# SCD4X-Grove.net
KiCad netlist of a schematic drawn in EAGLE
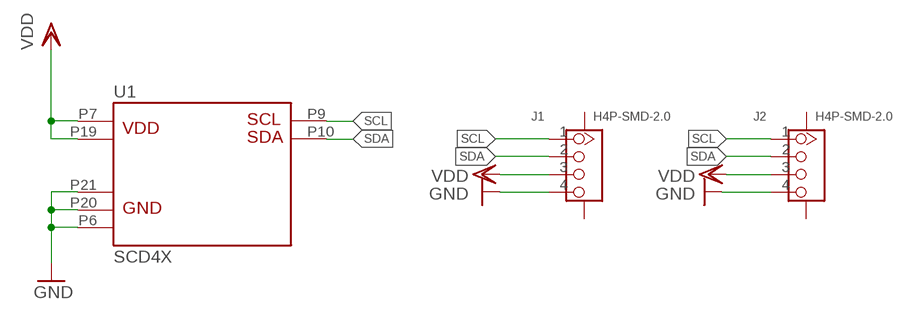
[diagram p0: schematic, sheet 1]

(export (version "E")
  (design (tool "Eeschema 10.0.6"))
  (components
    (comp (ref "J1")
      (value "H4P-SMD-2.0")
      (footprint "eagle-import:HW4-SMD-2.0")
      (libsource (lib "eagle-import") (part "GROVE-CONNECTOR-SMD(4+2P-2.0)"))
    )
    (comp (ref "J2")
      (value "H4P-SMD-2.0")
      (footprint "eagle-import:HW4-SMD-2.0")
      (libsource (lib "eagle-import") (part "GROVE-CONNECTOR-SMD(4+2P-2.0)"))
    )
    (comp (ref "U1")
      (value "SCD4X")
      (footprint "eagle-import:SCD4X")
      (libsource (lib "eagle-import") (part "SCD4X"))
    )
  )
  (nets
    (net (code "1") (name "GND") (class "Default")
      (node (ref "J1") (pin "4") (pinfunction "4_4") (pintype "bidirectional"))
      (node (ref "J2") (pin "4") (pinfunction "4_4") (pintype "bidirectional"))
      (node (ref "U1") (pin "P20") (pinfunction "P$20_P20") (pintype "power_in"))
      (node (ref "U1") (pin "P21") (pinfunction "P$21_P21") (pintype "power_in"))
      (node (ref "U1") (pin "P6") (pinfunction "P$6_P6") (pintype "power_in"))
    )
    (net (code "2") (name "SCL") (class "Default")
      (node (ref "J1") (pin "1") (pinfunction "1_1") (pintype "bidirectional"))
      (node (ref "J2") (pin "1") (pinfunction "1_1") (pintype "bidirectional"))
      (node (ref "U1") (pin "P9") (pinfunction "P$9_P9") (pintype "bidirectional"))
    )
    (net (code "3") (name "SDA") (class "Default")
      (node (ref "J1") (pin "2") (pinfunction "2_2") (pintype "bidirectional"))
      (node (ref "J2") (pin "2") (pinfunction "2_2") (pintype "bidirectional"))
      (node (ref "U1") (pin "P10") (pinfunction "P$10_P10") (pintype "bidirectional"))
    )
    (net (code "4") (name "VDD") (class "Default")
      (node (ref "J1") (pin "3") (pinfunction "3_3") (pintype "bidirectional"))
      (node (ref "J2") (pin "3") (pinfunction "3_3") (pintype "bidirectional"))
      (node (ref "U1") (pin "P19") (pinfunction "P$19_P19") (pintype "power_in"))
      (node (ref "U1") (pin "P7") (pinfunction "P$7_P7") (pintype "power_in"))
    )
    (net (code "5") (name "unconnected-(J1-PadSS1)") (class "Default")
      (node (ref "J1") (pin "SS1") (pinfunction "SS1_SS1") (pintype "bidirectional"))
    )
    (net (code "6") (name "unconnected-(J1-PadSS2)") (class "Default")
      (node (ref "J1") (pin "SS2") (pinfunction "SS2_SS2") (pintype "bidirectional"))
    )
    (net (code "7") (name "unconnected-(J2-PadSS1)") (class "Default")
      (node (ref "J2") (pin "SS1") (pinfunction "SS1_SS1") (pintype "bidirectional"))
    )
    (net (code "8") (name "unconnected-(J2-PadSS2)") (class "Default")
      (node (ref "J2") (pin "SS2") (pinfunction "SS2_SS2") (pintype "bidirectional"))
    )
    (net (code "9") (name "unconnected-(U1-P$1-PadP1)") (class "Default")
      (node (ref "U1") (pin "P1") (pinfunction "P$1_P1") (pintype "no_connect"))
    )
    (net (code "10") (name "unconnected-(U1-P$2-PadP2)") (class "Default")
      (node (ref "U1") (pin "P2") (pinfunction "P$2_P2") (pintype "no_connect"))
    )
    (net (code "11") (name "unconnected-(U1-P$3-PadP3)") (class "Default")
      (node (ref "U1") (pin "P3") (pinfunction "P$3_P3") (pintype "no_connect"))
    )
    (net (code "12") (name "unconnected-(U1-P$4-PadP4)") (class "Default")
      (node (ref "U1") (pin "P4") (pinfunction "P$4_P4") (pintype "no_connect"))
    )
    (net (code "13") (name "unconnected-(U1-P$5-PadP5)") (class "Default")
      (node (ref "U1") (pin "P5") (pinfunction "P$5_P5") (pintype "no_connect"))
    )
    (net (code "14") (name "unconnected-(U1-P$8-PadP8)") (class "Default")
      (node (ref "U1") (pin "P8") (pinfunction "P$8_P8") (pintype "no_connect"))
    )
    (net (code "15") (name "unconnected-(U1-P$11-PadP11)") (class "Default")
      (node (ref "U1") (pin "P11") (pinfunction "P$11_P11") (pintype "no_connect"))
    )
    (net (code "16") (name "unconnected-(U1-P$12-PadP12)") (class "Default")
      (node (ref "U1") (pin "P12") (pinfunction "P$12_P12") (pintype "no_connect"))
    )
    (net (code "17") (name "unconnected-(U1-P$13-PadP13)") (class "Default")
      (node (ref "U1") (pin "P13") (pinfunction "P$13_P13") (pintype "no_connect"))
    )
    (net (code "18") (name "unconnected-(U1-P$14-PadP14)") (class "Default")
      (node (ref "U1") (pin "P14") (pinfunction "P$14_P14") (pintype "no_connect"))
    )
    (net (code "19") (name "unconnected-(U1-P$15-PadP15)") (class "Default")
      (node (ref "U1") (pin "P15") (pinfunction "P$15_P15") (pintype "no_connect"))
    )
    (net (code "20") (name "unconnected-(U1-P$16-PadP16)") (class "Default")
      (node (ref "U1") (pin "P16") (pinfunction "P$16_P16") (pintype "no_connect"))
    )
    (net (code "21") (name "unconnected-(U1-P$17-PadP17)") (class "Default")
      (node (ref "U1") (pin "P17") (pinfunction "P$17_P17") (pintype "no_connect"))
    )
    (net (code "22") (name "unconnected-(U1-P$18-PadP18)") (class "Default")
      (node (ref "U1") (pin "P18") (pinfunction "P$18_P18") (pintype "no_connect"))
    )
  )
)
